# general_OpAmp.net
KiCad netlist of a schematic drawn in Altium Designer
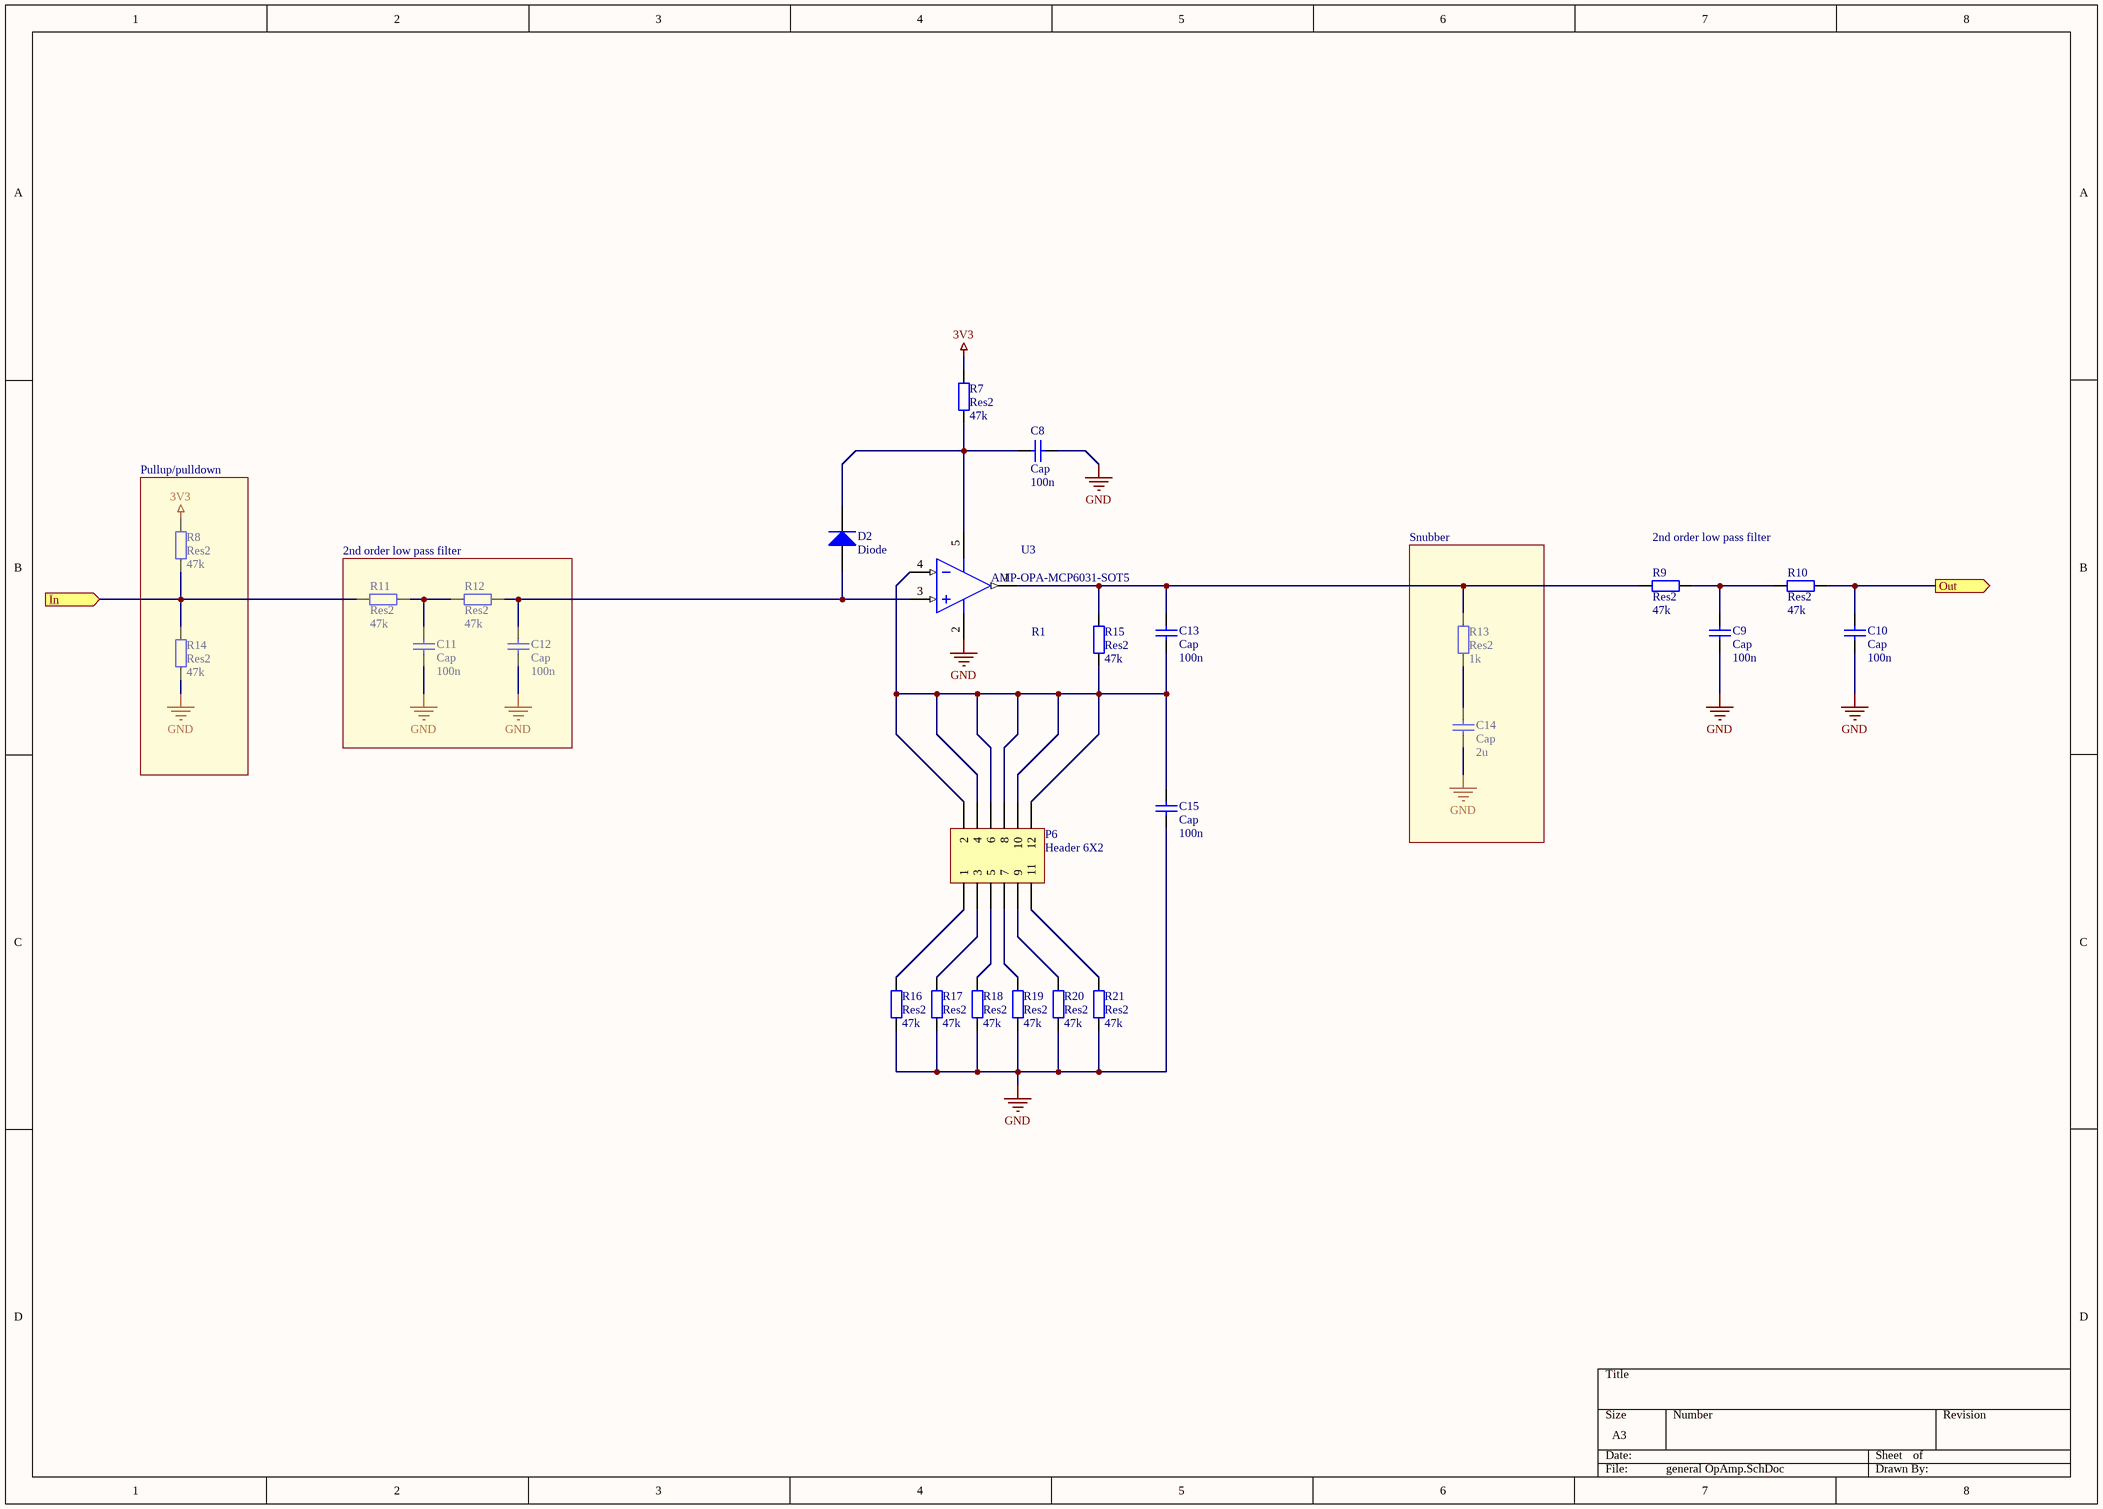
[diagram p0: general OpAmp.SchDoc]

(export (version "E")
  (design (tool "Eeschema 10.0.6"))
  (components
    (comp (ref "C8")
      (value "Cap")
      (footprint "SMD_Resistor_1206")
      (description "Capacitor")
      (fields (field (name "ALTIUM_VALUE") "100n") (field (name "PUBLISHER") "Altium Limited"))
      (libsource (lib "Miscellaneous Devices") (part "Cap"))
    )
    (comp (ref "C9")
      (value "Cap")
      (footprint "SMD_Resistor_1206")
      (description "Capacitor")
      (fields (field (name "ALTIUM_VALUE") "100n") (field (name "PUBLISHER") "Altium Limited"))
      (libsource (lib "Miscellaneous Devices") (part "Cap"))
    )
    (comp (ref "C10")
      (value "Cap")
      (footprint "SMD_Resistor_1206")
      (description "Capacitor")
      (fields (field (name "ALTIUM_VALUE") "100n") (field (name "PUBLISHER") "Altium Limited"))
      (libsource (lib "Miscellaneous Devices") (part "Cap"))
    )
    (comp (ref "C11")
      (value "Cap")
      (footprint "SMD_Resistor_1206")
      (description "Capacitor")
      (fields (field (name "ALTIUM_VALUE") "100n") (field (name "PUBLISHER") "Altium Limited"))
      (libsource (lib "Miscellaneous Devices") (part "Cap"))
    )
    (comp (ref "C12")
      (value "Cap")
      (footprint "SMD_Resistor_1206")
      (description "Capacitor")
      (fields (field (name "ALTIUM_VALUE") "100n") (field (name "PUBLISHER") "Altium Limited"))
      (libsource (lib "Miscellaneous Devices") (part "Cap"))
    )
    (comp (ref "C13")
      (value "Cap")
      (footprint "SMD_Resistor_1206")
      (description "Capacitor")
      (fields (field (name "ALTIUM_VALUE") "100n") (field (name "PUBLISHER") "Altium Limited"))
      (libsource (lib "Miscellaneous Devices") (part "Cap"))
    )
    (comp (ref "C14")
      (value "Cap")
      (footprint "SMD_Resistor_1206")
      (description "Capacitor")
      (fields (field (name "ALTIUM_VALUE") "2u") (field (name "PUBLISHER") "Altium Limited"))
      (libsource (lib "Miscellaneous Devices") (part "Cap"))
    )
    (comp (ref "C15")
      (value "Cap")
      (footprint "SMD_Resistor_1206")
      (description "Capacitor")
      (fields (field (name "ALTIUM_VALUE") "100n") (field (name "PUBLISHER") "Altium Limited"))
      (libsource (lib "Miscellaneous Devices") (part "Cap"))
    )
    (comp (ref "D2")
      (value "Diode")
      (footprint "SMD_Resistor_1206")
      (description "Default Diode")
      (fields (field (name "PUBLISHER") "Altium Limited"))
      (libsource (lib "Miscellaneous Devices") (part "Diode"))
    )
    (comp (ref "P6")
      (value "Header 6X2")
      (footprint "HDR2X6")
      (description "Header, 6-Pin, Dual row")
      (fields (field (name "PUBLISHER") "Altium Limited"))
      (libsource (lib "Miscellaneous Connectors") (part "Header 6X2"))
    )
    (comp (ref "R7")
      (value "Res2")
      (footprint "SMD_Resistor_1206")
      (description "Resistor")
      (fields (field (name "ALTIUM_VALUE") "47k") (field (name "PUBLISHER") "Altium Limited"))
      (libsource (lib "") (part "Res2_1"))
    )
    (comp (ref "R8")
      (value "Res2")
      (footprint "SMD_Resistor_1206")
      (description "Resistor")
      (fields (field (name "ALTIUM_VALUE") "47k") (field (name "PUBLISHER") "Altium Limited"))
      (libsource (lib "") (part "Res2_2"))
    )
    (comp (ref "R9")
      (value "Res2")
      (footprint "SMD_Resistor_1206")
      (description "Resistor")
      (fields (field (name "ALTIUM_VALUE") "47k") (field (name "PUBLISHER") "Altium Limited"))
      (libsource (lib "Miscellaneous Devices") (part "Res2"))
    )
    (comp (ref "R10")
      (value "Res2")
      (footprint "SMD_Resistor_1206")
      (description "Resistor")
      (fields (field (name "ALTIUM_VALUE") "47k") (field (name "PUBLISHER") "Altium Limited"))
      (libsource (lib "Miscellaneous Devices") (part "Res2"))
    )
    (comp (ref "R11")
      (value "Res2")
      (footprint "SMD_Resistor_1206")
      (description "Resistor")
      (fields (field (name "ALTIUM_VALUE") "47k") (field (name "PUBLISHER") "Altium Limited"))
      (libsource (lib "Miscellaneous Devices") (part "Res2"))
    )
    (comp (ref "R12")
      (value "Res2")
      (footprint "SMD_Resistor_1206")
      (description "Resistor")
      (fields (field (name "ALTIUM_VALUE") "47k") (field (name "PUBLISHER") "Altium Limited"))
      (libsource (lib "Miscellaneous Devices") (part "Res2"))
    )
    (comp (ref "R13")
      (value "Res2")
      (footprint "SMD_Resistor_1206")
      (description "Resistor")
      (fields (field (name "ALTIUM_VALUE") "1k") (field (name "PUBLISHER") "Altium Limited"))
      (libsource (lib "Miscellaneous Devices") (part "Res2"))
    )
    (comp (ref "R14")
      (value "Res2")
      (footprint "SMD_Resistor_1206")
      (description "Resistor")
      (fields (field (name "ALTIUM_VALUE") "47k") (field (name "PUBLISHER") "Altium Limited"))
      (libsource (lib "") (part "Res2_2"))
    )
    (comp (ref "R15")
      (value "Res2")
      (footprint "SMD_Resistor_1206")
      (description "Resistor")
      (fields (field (name "ALTIUM_VALUE") "47k") (field (name "PUBLISHER") "Altium Limited"))
      (libsource (lib "Miscellaneous Devices") (part "Res2"))
    )
    (comp (ref "R16")
      (value "Res2")
      (footprint "SMD_Resistor_1206")
      (description "Resistor")
      (fields (field (name "ALTIUM_VALUE") "47k") (field (name "PUBLISHER") "Altium Limited"))
      (libsource (lib "Miscellaneous Devices") (part "Res2"))
    )
    (comp (ref "R17")
      (value "Res2")
      (footprint "SMD_Resistor_1206")
      (description "Resistor")
      (fields (field (name "ALTIUM_VALUE") "47k") (field (name "PUBLISHER") "Altium Limited"))
      (libsource (lib "Miscellaneous Devices") (part "Res2"))
    )
    (comp (ref "R18")
      (value "Res2")
      (footprint "SMD_Resistor_1206")
      (description "Resistor")
      (fields (field (name "ALTIUM_VALUE") "47k") (field (name "PUBLISHER") "Altium Limited"))
      (libsource (lib "Miscellaneous Devices") (part "Res2"))
    )
    (comp (ref "R19")
      (value "Res2")
      (footprint "SMD_Resistor_1206")
      (description "Resistor")
      (fields (field (name "ALTIUM_VALUE") "47k") (field (name "PUBLISHER") "Altium Limited"))
      (libsource (lib "Miscellaneous Devices") (part "Res2"))
    )
    (comp (ref "R20")
      (value "Res2")
      (footprint "SMD_Resistor_1206")
      (description "Resistor")
      (fields (field (name "ALTIUM_VALUE") "47k") (field (name "PUBLISHER") "Altium Limited"))
      (libsource (lib "Miscellaneous Devices") (part "Res2"))
    )
    (comp (ref "R21")
      (value "Res2")
      (footprint "SMD_Resistor_1206")
      (description "Resistor")
      (fields (field (name "ALTIUM_VALUE") "47k") (field (name "PUBLISHER") "Altium Limited"))
      (libsource (lib "Miscellaneous Devices") (part "Res2"))
    )
    (comp (ref "U3")
      (value "AMP-OPA-MCP6031-SOT5")
      (footprint "SOT-23-OT5_M")
      (libsource (lib "AMP-OPA-MCP6031-SOT5") (part "AMP-OPA-MCP6031-SOT5"))
    )
  )
  (nets
    (net (code "1") (name "/In") (class "Default")
      (node (ref "R11") (pin "1") (pinfunction "1_1") (pintype "passive"))
      (node (ref "R14") (pin "1") (pinfunction "1_1") (pintype "passive"))
      (node (ref "R8") (pin "2") (pinfunction "2_2") (pintype "passive"))
    )
    (net (code "2") (name "/Out") (class "Default")
      (node (ref "C10") (pin "2") (pinfunction "2_2") (pintype "passive"))
      (node (ref "R10") (pin "2") (pinfunction "2_2") (pintype "passive"))
    )
    (net (code "3") (name "3V3") (class "Default")
      (node (ref "R7") (pin "1") (pinfunction "1_1") (pintype "passive"))
      (node (ref "R8") (pin "1") (pinfunction "1_1") (pintype "passive"))
    )
    (net (code "4") (name "GND") (class "Default")
      (node (ref "C10") (pin "1") (pinfunction "1_1") (pintype "passive"))
      (node (ref "C11") (pin "1") (pinfunction "1_1") (pintype "passive"))
      (node (ref "C12") (pin "1") (pinfunction "1_1") (pintype "passive"))
      (node (ref "C14") (pin "1") (pinfunction "1_1") (pintype "passive"))
      (node (ref "C15") (pin "1") (pinfunction "1_1") (pintype "passive"))
      (node (ref "C8") (pin "2") (pinfunction "2_2") (pintype "passive"))
      (node (ref "C9") (pin "1") (pinfunction "1_1") (pintype "passive"))
      (node (ref "R14") (pin "2") (pinfunction "2_2") (pintype "passive"))
      (node (ref "R16") (pin "1") (pinfunction "1_1") (pintype "passive"))
      (node (ref "R17") (pin "1") (pinfunction "1_1") (pintype "passive"))
      (node (ref "R18") (pin "1") (pinfunction "1_1") (pintype "passive"))
      (node (ref "R19") (pin "1") (pinfunction "1_1") (pintype "passive"))
      (node (ref "R20") (pin "1") (pinfunction "1_1") (pintype "passive"))
      (node (ref "R21") (pin "1") (pinfunction "1_1") (pintype "passive"))
      (node (ref "U3") (pin "2") (pinfunction "VSS_2") (pintype "power_in"))
    )
    (net (code "5") (name "Net-(C9-Pad2)") (class "Default")
      (node (ref "C9") (pin "2") (pinfunction "2_2") (pintype "passive"))
      (node (ref "R10") (pin "1") (pinfunction "1_1") (pintype "passive"))
      (node (ref "R9") (pin "2") (pinfunction "2_2") (pintype "passive"))
    )
    (net (code "6") (name "Net-(C11-Pad2)") (class "Default")
      (node (ref "C11") (pin "2") (pinfunction "2_2") (pintype "passive"))
      (node (ref "R11") (pin "2") (pinfunction "2_2") (pintype "passive"))
      (node (ref "R12") (pin "1") (pinfunction "1_1") (pintype "passive"))
    )
    (net (code "7") (name "Net-(C14-Pad2)") (class "Default")
      (node (ref "C14") (pin "2") (pinfunction "2_2") (pintype "passive"))
      (node (ref "R13") (pin "1") (pinfunction "1_1") (pintype "passive"))
    )
    (net (code "8") (name "Net-(D2-A)") (class "Default")
      (node (ref "C12") (pin "2") (pinfunction "2_2") (pintype "passive"))
      (node (ref "D2") (pin "1") (pinfunction "A_1") (pintype "passive"))
      (node (ref "R12") (pin "2") (pinfunction "2_2") (pintype "passive"))
      (node (ref "U3") (pin "3") (pinfunction "VIN+_3") (pintype "input"))
    )
    (net (code "9") (name "Net-(D2-K)") (class "Default")
      (node (ref "C8") (pin "1") (pinfunction "1_1") (pintype "passive"))
      (node (ref "D2") (pin "2") (pinfunction "K_2") (pintype "passive"))
      (node (ref "R7") (pin "2") (pinfunction "2_2") (pintype "passive"))
      (node (ref "U3") (pin "5") (pinfunction "VDD_5") (pintype "power_in"))
    )
    (net (code "10") (name "Net-(P6-Pad1)") (class "Default")
      (node (ref "P6") (pin "1") (pinfunction "1_1") (pintype "passive"))
      (node (ref "R16") (pin "2") (pinfunction "2_2") (pintype "passive"))
    )
    (net (code "11") (name "Net-(P6-Pad3)") (class "Default")
      (node (ref "P6") (pin "3") (pinfunction "3_3") (pintype "passive"))
      (node (ref "R17") (pin "2") (pinfunction "2_2") (pintype "passive"))
    )
    (net (code "12") (name "Net-(P6-Pad5)") (class "Default")
      (node (ref "P6") (pin "5") (pinfunction "5_5") (pintype "passive"))
      (node (ref "R18") (pin "2") (pinfunction "2_2") (pintype "passive"))
    )
    (net (code "13") (name "Net-(P6-Pad7)") (class "Default")
      (node (ref "P6") (pin "7") (pinfunction "7_7") (pintype "passive"))
      (node (ref "R19") (pin "2") (pinfunction "2_2") (pintype "passive"))
    )
    (net (code "14") (name "Net-(P6-Pad9)") (class "Default")
      (node (ref "P6") (pin "9") (pinfunction "9_9") (pintype "passive"))
      (node (ref "R20") (pin "2") (pinfunction "2_2") (pintype "passive"))
    )
    (net (code "15") (name "Net-(P6-Pad11)") (class "Default")
      (node (ref "P6") (pin "11") (pinfunction "11_11") (pintype "passive"))
      (node (ref "R21") (pin "2") (pinfunction "2_2") (pintype "passive"))
    )
    (net (code "16") (name "Net-(U3-VIN-)") (class "Default")
      (node (ref "C13") (pin "1") (pinfunction "1_1") (pintype "passive"))
      (node (ref "C15") (pin "2") (pinfunction "2_2") (pintype "passive"))
      (node (ref "P6") (pin "10") (pinfunction "10_10") (pintype "passive"))
      (node (ref "P6") (pin "12") (pinfunction "12_12") (pintype "passive"))
      (node (ref "P6") (pin "2") (pinfunction "2_2") (pintype "passive"))
      (node (ref "P6") (pin "4") (pinfunction "4_4") (pintype "passive"))
      (node (ref "P6") (pin "6") (pinfunction "6_6") (pintype "passive"))
      (node (ref "P6") (pin "8") (pinfunction "8_8") (pintype "passive"))
      (node (ref "R15") (pin "1") (pinfunction "1_1") (pintype "passive"))
      (node (ref "U3") (pin "4") (pinfunction "VIN-_4") (pintype "input"))
    )
    (net (code "17") (name "Net-(U3-VOUT)") (class "Default")
      (node (ref "C13") (pin "2") (pinfunction "2_2") (pintype "passive"))
      (node (ref "R13") (pin "2") (pinfunction "2_2") (pintype "passive"))
      (node (ref "R15") (pin "2") (pinfunction "2_2") (pintype "passive"))
      (node (ref "R9") (pin "1") (pinfunction "1_1") (pintype "passive"))
      (node (ref "U3") (pin "1") (pinfunction "VOUT_1") (pintype "output"))
    )
  )
)
